# connector.net
KiCad netlist of a schematic drawn in Altium Designer
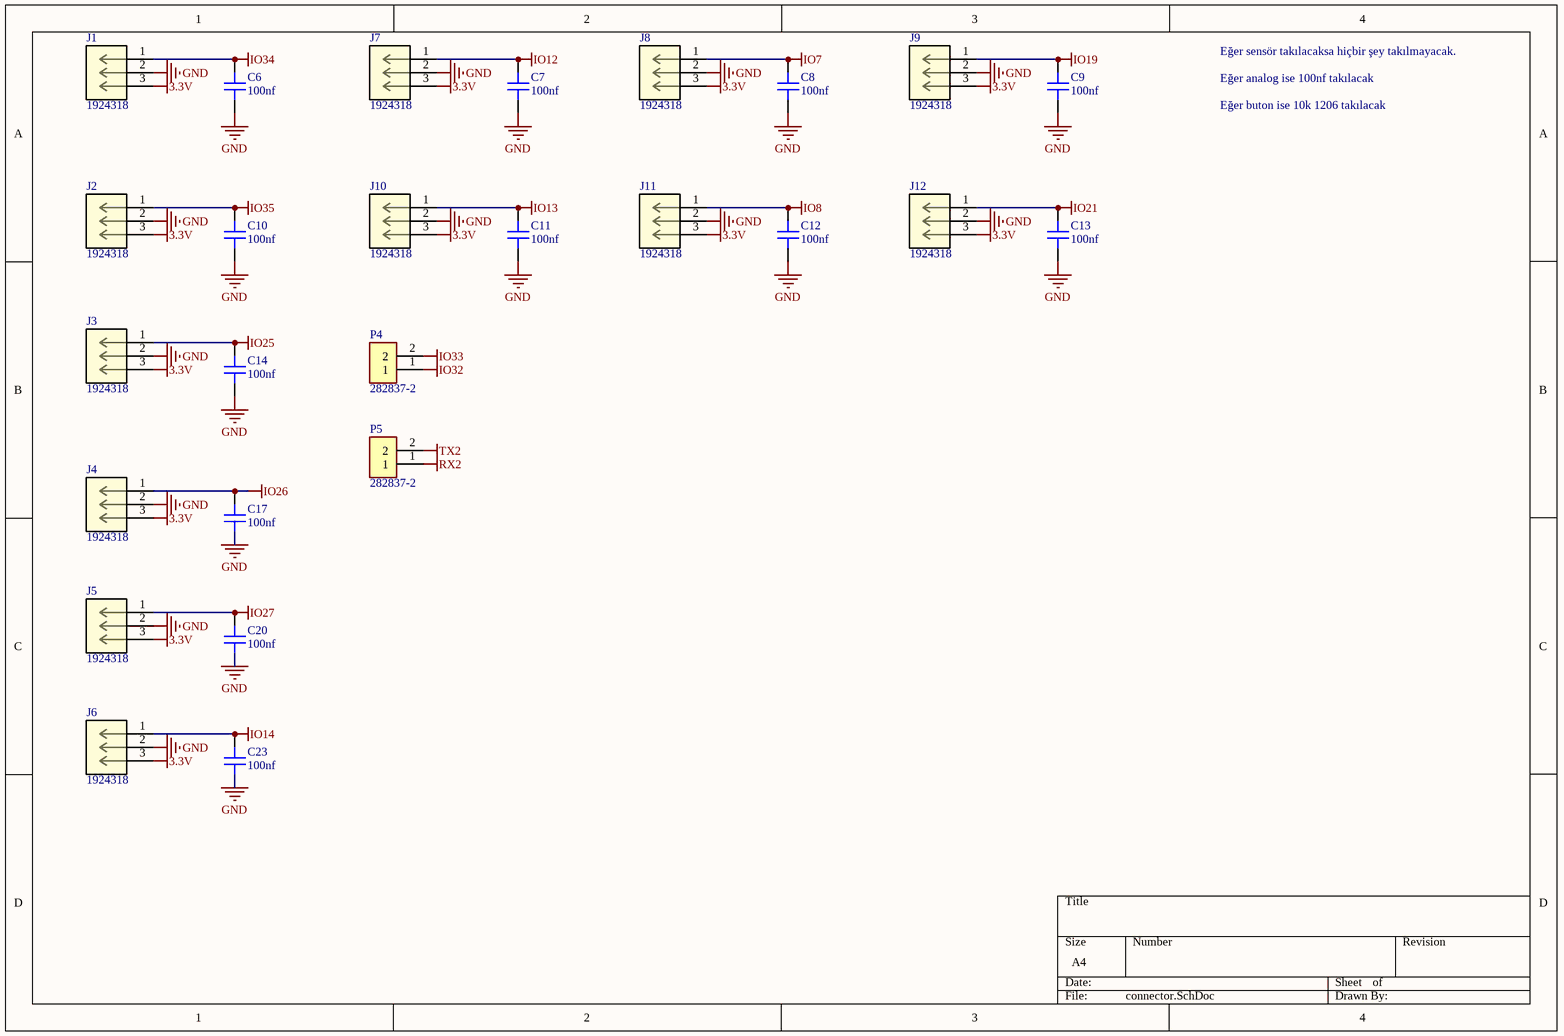
[diagram p0: connector.SchDoc]

(export (version "E")
  (design (tool "Eeschema 10.0.6"))
  (components
    (comp (ref "C6")
      (value "100nf")
      (footprint "CAP 1206_3216 - 0.8MM")
      (description "CAP CER 1000PF 200V X7R 1206")
      (fields (field (name "PART NUMBER") "MM062C102KCZ2A") (field (name "MANUFACTURER") "AVX Corporation"))
      (libsource (lib "Celestial Altium Library - altium_library") (part "Capacitor"))
    )
    (comp (ref "C7")
      (value "100nf")
      (footprint "CAP 1206_3216 - 0.8MM")
      (description "CAP CER 1000PF 200V X7R 1206")
      (fields (field (name "PART NUMBER") "MM062C102KCZ2A") (field (name "MANUFACTURER") "AVX Corporation"))
      (libsource (lib "Celestial Altium Library - altium_library") (part "Capacitor"))
    )
    (comp (ref "C8")
      (value "100nf")
      (footprint "CAP 1206_3216 - 0.8MM")
      (description "CAP CER 1000PF 200V X7R 1206")
      (fields (field (name "PART NUMBER") "MM062C102KCZ2A") (field (name "MANUFACTURER") "AVX Corporation"))
      (libsource (lib "Celestial Altium Library - altium_library") (part "Capacitor"))
    )
    (comp (ref "C9")
      (value "100nf")
      (footprint "CAP 1206_3216 - 0.8MM")
      (description "CAP CER 1000PF 200V X7R 1206")
      (fields (field (name "PART NUMBER") "MM062C102KCZ2A") (field (name "MANUFACTURER") "AVX Corporation"))
      (libsource (lib "Celestial Altium Library - altium_library") (part "Capacitor"))
    )
    (comp (ref "C10")
      (value "100nf")
      (footprint "CAP 1206_3216 - 0.8MM")
      (description "CAP CER 1000PF 200V X7R 1206")
      (fields (field (name "PART NUMBER") "MM062C102KCZ2A") (field (name "MANUFACTURER") "AVX Corporation"))
      (libsource (lib "Celestial Altium Library - altium_library") (part "Capacitor"))
    )
    (comp (ref "C11")
      (value "100nf")
      (footprint "CAP 1206_3216 - 0.8MM")
      (description "CAP CER 1000PF 200V X7R 1206")
      (fields (field (name "PART NUMBER") "MM062C102KCZ2A") (field (name "MANUFACTURER") "AVX Corporation"))
      (libsource (lib "Celestial Altium Library - altium_library") (part "Capacitor"))
    )
    (comp (ref "C12")
      (value "100nf")
      (footprint "CAP 1206_3216 - 0.8MM")
      (description "CAP CER 1000PF 200V X7R 1206")
      (fields (field (name "PART NUMBER") "MM062C102KCZ2A") (field (name "MANUFACTURER") "AVX Corporation"))
      (libsource (lib "Celestial Altium Library - altium_library") (part "Capacitor"))
    )
    (comp (ref "C13")
      (value "100nf")
      (footprint "CAP 1206_3216 - 0.8MM")
      (description "CAP CER 1000PF 200V X7R 1206")
      (fields (field (name "PART NUMBER") "MM062C102KCZ2A") (field (name "MANUFACTURER") "AVX Corporation"))
      (libsource (lib "Celestial Altium Library - altium_library") (part "Capacitor"))
    )
    (comp (ref "C14")
      (value "100nf")
      (footprint "CAP 1206_3216 - 0.8MM")
      (description "CAP CER 1000PF 200V X7R 1206")
      (fields (field (name "PART NUMBER") "MM062C102KCZ2A") (field (name "MANUFACTURER") "AVX Corporation"))
      (libsource (lib "Celestial Altium Library - altium_library") (part "Capacitor"))
    )
    (comp (ref "C17")
      (value "100nf")
      (footprint "CAP 1206_3216 - 0.8MM")
      (description "CAP CER 1000PF 200V X7R 1206")
      (fields (field (name "PART NUMBER") "MM062C102KCZ2A") (field (name "MANUFACTURER") "AVX Corporation"))
      (libsource (lib "Celestial Altium Library - altium_library") (part "Capacitor"))
    )
    (comp (ref "C20")
      (value "100nf")
      (footprint "CAP 1206_3216 - 0.8MM")
      (description "CAP CER 1000PF 200V X7R 1206")
      (fields (field (name "PART NUMBER") "MM062C102KCZ2A") (field (name "MANUFACTURER") "AVX Corporation"))
      (libsource (lib "Celestial Altium Library - altium_library") (part "Capacitor"))
    )
    (comp (ref "C23")
      (value "100nf")
      (footprint "CAP 1206_3216 - 0.8MM")
      (description "CAP CER 1000PF 200V X7R 1206")
      (fields (field (name "PART NUMBER") "MM062C102KCZ2A") (field (name "MANUFACTURER") "AVX Corporation"))
      (libsource (lib "Celestial Altium Library - altium_library") (part "Capacitor"))
    )
    (comp (ref "J1")
      (value "1924318")
      (footprint "CONN_1924318")
      (description "No Description Available")
      (libsource (lib "1924318") (part "1924318"))
    )
    (comp (ref "J2")
      (value "1924318")
      (footprint "CONN_1924318")
      (description "No Description Available")
      (libsource (lib "1924318") (part "1924318"))
    )
    (comp (ref "J3")
      (value "1924318")
      (footprint "CONN_1924318")
      (description "No Description Available")
      (libsource (lib "1924318") (part "1924318"))
    )
    (comp (ref "J4")
      (value "1924318")
      (footprint "CONN_1924318")
      (description "No Description Available")
      (libsource (lib "1924318") (part "1924318"))
    )
    (comp (ref "J5")
      (value "1924318")
      (footprint "CONN_1924318")
      (description "No Description Available")
      (libsource (lib "1924318") (part "1924318"))
    )
    (comp (ref "J6")
      (value "1924318")
      (footprint "CONN_1924318")
      (description "No Description Available")
      (libsource (lib "1924318") (part "1924318"))
    )
    (comp (ref "J7")
      (value "1924318")
      (footprint "CONN_1924318")
      (description "No Description Available")
      (libsource (lib "1924318") (part "1924318"))
    )
    (comp (ref "J8")
      (value "1924318")
      (footprint "CONN_1924318")
      (description "No Description Available")
      (libsource (lib "1924318") (part "1924318"))
    )
    (comp (ref "J9")
      (value "1924318")
      (footprint "CONN_1924318")
      (description "No Description Available")
      (libsource (lib "1924318") (part "1924318"))
    )
    (comp (ref "J10")
      (value "1924318")
      (footprint "CONN_1924318")
      (description "No Description Available")
      (libsource (lib "1924318") (part "1924318"))
    )
    (comp (ref "J11")
      (value "1924318")
      (footprint "CONN_1924318")
      (description "No Description Available")
      (libsource (lib "1924318") (part "1924318"))
    )
    (comp (ref "J12")
      (value "1924318")
      (footprint "CONN_1924318")
      (description "No Description Available")
      (libsource (lib "1924318") (part "1924318"))
    )
    (comp (ref "P4")
      (value "282837-2")
      (footprint "TE_282837-2")
      (fields (field (name "MF") "TE Connectivity"))
      (libsource (lib "connector") (part "282837-2"))
    )
    (comp (ref "P5")
      (value "282837-2")
      (footprint "TE_282837-2")
      (fields (field (name "MF") "TE Connectivity"))
      (libsource (lib "connector") (part "282837-2"))
    )
  )
  (nets
    (net (code "1") (name "3.3V") (class "Default")
      (node (ref "J1") (pin "3") (pinfunction "3_3") (pintype "passive"))
      (node (ref "J10") (pin "3") (pinfunction "3_3") (pintype "passive"))
      (node (ref "J11") (pin "3") (pinfunction "3_3") (pintype "passive"))
      (node (ref "J12") (pin "3") (pinfunction "3_3") (pintype "passive"))
      (node (ref "J2") (pin "3") (pinfunction "3_3") (pintype "passive"))
      (node (ref "J3") (pin "3") (pinfunction "3_3") (pintype "passive"))
      (node (ref "J4") (pin "3") (pinfunction "3_3") (pintype "passive"))
      (node (ref "J5") (pin "3") (pinfunction "3_3") (pintype "passive"))
      (node (ref "J6") (pin "3") (pinfunction "3_3") (pintype "passive"))
      (node (ref "J7") (pin "3") (pinfunction "3_3") (pintype "passive"))
      (node (ref "J8") (pin "3") (pinfunction "3_3") (pintype "passive"))
      (node (ref "J9") (pin "3") (pinfunction "3_3") (pintype "passive"))
    )
    (net (code "2") (name "GND") (class "Default")
      (node (ref "C10") (pin "1") (pinfunction "1_1") (pintype "passive"))
      (node (ref "C11") (pin "1") (pinfunction "1_1") (pintype "passive"))
      (node (ref "C12") (pin "1") (pinfunction "1_1") (pintype "passive"))
      (node (ref "C13") (pin "1") (pinfunction "1_1") (pintype "passive"))
      (node (ref "C14") (pin "1") (pinfunction "1_1") (pintype "passive"))
      (node (ref "C17") (pin "1") (pinfunction "1_1") (pintype "passive"))
      (node (ref "C20") (pin "1") (pinfunction "1_1") (pintype "passive"))
      (node (ref "C23") (pin "1") (pinfunction "1_1") (pintype "passive"))
      (node (ref "C6") (pin "1") (pinfunction "1_1") (pintype "passive"))
      (node (ref "C7") (pin "1") (pinfunction "1_1") (pintype "passive"))
      (node (ref "C8") (pin "1") (pinfunction "1_1") (pintype "passive"))
      (node (ref "C9") (pin "1") (pinfunction "1_1") (pintype "passive"))
      (node (ref "J1") (pin "2") (pinfunction "2_2") (pintype "passive"))
      (node (ref "J10") (pin "2") (pinfunction "2_2") (pintype "passive"))
      (node (ref "J11") (pin "2") (pinfunction "2_2") (pintype "passive"))
      (node (ref "J12") (pin "2") (pinfunction "2_2") (pintype "passive"))
      (node (ref "J2") (pin "2") (pinfunction "2_2") (pintype "passive"))
      (node (ref "J3") (pin "2") (pinfunction "2_2") (pintype "passive"))
      (node (ref "J4") (pin "2") (pinfunction "2_2") (pintype "passive"))
      (node (ref "J5") (pin "2") (pinfunction "2_2") (pintype "passive"))
      (node (ref "J6") (pin "2") (pinfunction "2_2") (pintype "passive"))
      (node (ref "J7") (pin "2") (pinfunction "2_2") (pintype "passive"))
      (node (ref "J8") (pin "2") (pinfunction "2_2") (pintype "passive"))
      (node (ref "J9") (pin "2") (pinfunction "2_2") (pintype "passive"))
    )
    (net (code "3") (name "IO7") (class "Default")
      (node (ref "C8") (pin "2") (pinfunction "2_2") (pintype "passive"))
      (node (ref "J8") (pin "1") (pinfunction "1_1") (pintype "passive"))
    )
    (net (code "4") (name "IO8") (class "Default")
      (node (ref "C12") (pin "2") (pinfunction "2_2") (pintype "passive"))
      (node (ref "J11") (pin "1") (pinfunction "1_1") (pintype "passive"))
    )
    (net (code "5") (name "IO12") (class "Default")
      (node (ref "C7") (pin "2") (pinfunction "2_2") (pintype "passive"))
      (node (ref "J7") (pin "1") (pinfunction "1_1") (pintype "passive"))
    )
    (net (code "6") (name "IO13") (class "Default")
      (node (ref "C11") (pin "2") (pinfunction "2_2") (pintype "passive"))
      (node (ref "J10") (pin "1") (pinfunction "1_1") (pintype "passive"))
    )
    (net (code "7") (name "IO14") (class "Default")
      (node (ref "C23") (pin "2") (pinfunction "2_2") (pintype "passive"))
      (node (ref "J6") (pin "1") (pinfunction "1_1") (pintype "passive"))
    )
    (net (code "8") (name "IO19") (class "Default")
      (node (ref "C9") (pin "2") (pinfunction "2_2") (pintype "passive"))
      (node (ref "J9") (pin "1") (pinfunction "1_1") (pintype "passive"))
    )
    (net (code "9") (name "IO21") (class "Default")
      (node (ref "C13") (pin "2") (pinfunction "2_2") (pintype "passive"))
      (node (ref "J12") (pin "1") (pinfunction "1_1") (pintype "passive"))
    )
    (net (code "10") (name "IO25") (class "Default")
      (node (ref "C14") (pin "2") (pinfunction "2_2") (pintype "passive"))
      (node (ref "J3") (pin "1") (pinfunction "1_1") (pintype "passive"))
    )
    (net (code "11") (name "IO26") (class "Default")
      (node (ref "C17") (pin "2") (pinfunction "2_2") (pintype "passive"))
      (node (ref "J4") (pin "1") (pinfunction "1_1") (pintype "passive"))
    )
    (net (code "12") (name "IO27") (class "Default")
      (node (ref "C20") (pin "2") (pinfunction "2_2") (pintype "passive"))
      (node (ref "J5") (pin "1") (pinfunction "1_1") (pintype "passive"))
    )
    (net (code "13") (name "IO32") (class "Default")
      (node (ref "P4") (pin "1") (pinfunction "1_1") (pintype "passive"))
    )
    (net (code "14") (name "IO33") (class "Default")
      (node (ref "P4") (pin "2") (pinfunction "2_2") (pintype "passive"))
    )
    (net (code "15") (name "IO34") (class "Default")
      (node (ref "C6") (pin "2") (pinfunction "2_2") (pintype "passive"))
      (node (ref "J1") (pin "1") (pinfunction "1_1") (pintype "passive"))
    )
    (net (code "16") (name "IO35") (class "Default")
      (node (ref "C10") (pin "2") (pinfunction "2_2") (pintype "passive"))
      (node (ref "J2") (pin "1") (pinfunction "1_1") (pintype "passive"))
    )
    (net (code "17") (name "RX2") (class "Default")
      (node (ref "P5") (pin "1") (pinfunction "1_1") (pintype "passive"))
    )
    (net (code "18") (name "TX2") (class "Default")
      (node (ref "P5") (pin "2") (pinfunction "2_2") (pintype "passive"))
    )
  )
)
